# schmtc.net
KiCad netlist of a schematic drawn in EAGLE
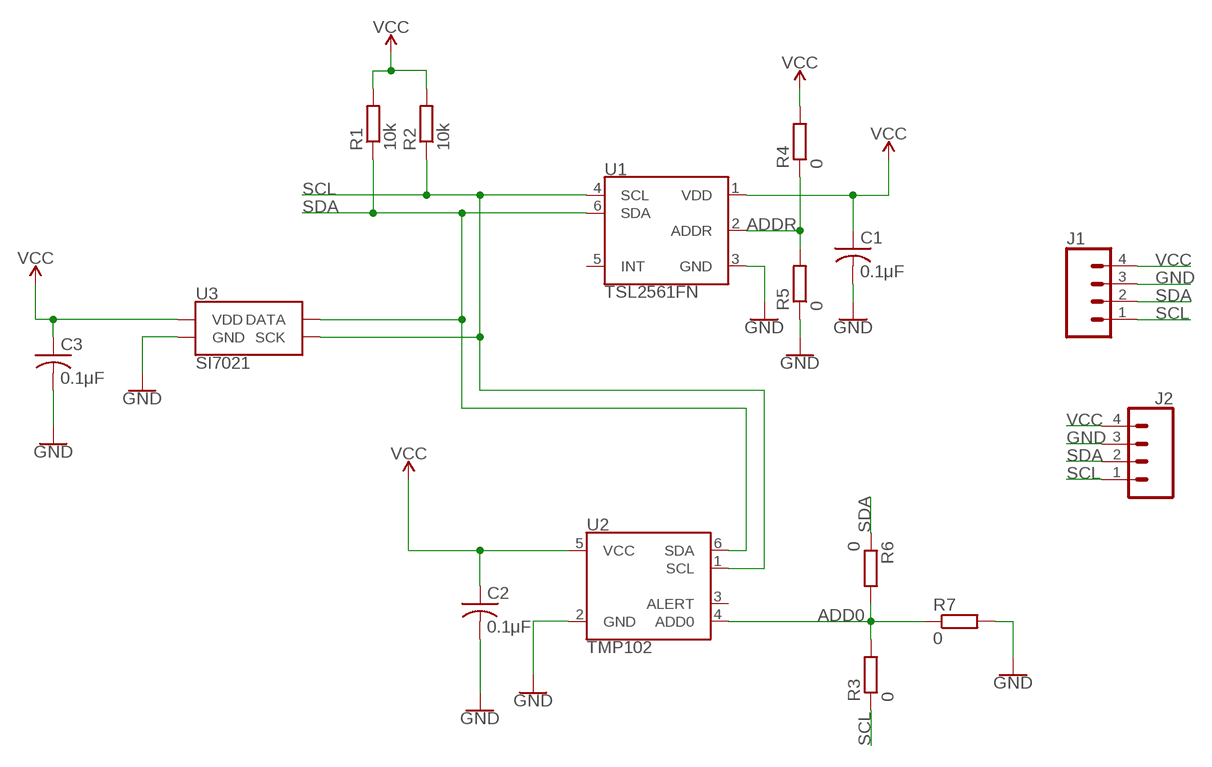
[diagram p0: schematic, sheet 1]

(export (version "E")
  (design (tool "Eeschema 10.0.6"))
  (components
    (comp (ref "C1")
      (value "0.1μF")
      (footprint "eagle-import:C0603")
      (libsource (lib "eagle-import") (part "C-USC0603"))
    )
    (comp (ref "C2")
      (value "0.1μF")
      (footprint "eagle-import:C0603")
      (libsource (lib "eagle-import") (part "C-USC0603"))
    )
    (comp (ref "C3")
      (value "0.1μF")
      (footprint "eagle-import:C0603")
      (libsource (lib "eagle-import") (part "C-USC0603"))
    )
    (comp (ref "J1")
      (value "CONN_04")
      (footprint "eagle-import:1X04")
      (libsource (lib "eagle-import") (part "CONN_04"))
    )
    (comp (ref "J2")
      (value "CONN_04")
      (footprint "eagle-import:1X04")
      (libsource (lib "eagle-import") (part "CONN_04"))
    )
    (comp (ref "R1")
      (value "10k")
      (footprint "eagle-import:R0603")
      (libsource (lib "eagle-import") (part "R-EU_R0603"))
    )
    (comp (ref "R2")
      (value "10k")
      (footprint "eagle-import:R0603")
      (libsource (lib "eagle-import") (part "R-EU_R0603"))
    )
    (comp (ref "R3")
      (value "0")
      (footprint "eagle-import:R0603")
      (libsource (lib "eagle-import") (part "R-EU_R0603"))
    )
    (comp (ref "R4")
      (value "0")
      (footprint "eagle-import:R0603")
      (libsource (lib "eagle-import") (part "R-EU_R0603"))
    )
    (comp (ref "R5")
      (value "0")
      (footprint "eagle-import:R0603")
      (libsource (lib "eagle-import") (part "R-EU_R0603"))
    )
    (comp (ref "R6")
      (value "0")
      (footprint "eagle-import:R0603")
      (libsource (lib "eagle-import") (part "R-EU_R0603"))
    )
    (comp (ref "R7")
      (value "0")
      (footprint "eagle-import:R0603")
      (libsource (lib "eagle-import") (part "R-EU_R0603"))
    )
    (comp (ref "U1")
      (value "TSL2561FN")
      (footprint "eagle-import:DFN-6-2X2")
      (libsource (lib "eagle-import") (part "TSL2561FN"))
    )
    (comp (ref "U2")
      (value "TMP102")
      (footprint "eagle-import:SOT563")
      (libsource (lib "eagle-import") (part "TMP102"))
    )
    (comp (ref "U3")
      (value "SI7021")
      (footprint "eagle-import:DFN-6-3X3-SI7021")
      (libsource (lib "eagle-import") (part "SI7021"))
    )
  )
  (nets
    (net (code "1") (name "/ADD0") (class "Default")
      (node (ref "R3") (pin "2") (pinfunction "2_2") (pintype "passive"))
      (node (ref "R6") (pin "2") (pinfunction "2_2") (pintype "passive"))
      (node (ref "R7") (pin "1") (pinfunction "1_1") (pintype "passive"))
      (node (ref "U2") (pin "4") (pinfunction "ADD0_4") (pintype "bidirectional"))
    )
    (net (code "2") (name "/ADDR") (class "Default")
      (node (ref "R4") (pin "1") (pinfunction "1_1") (pintype "passive"))
      (node (ref "R5") (pin "2") (pinfunction "2_2") (pintype "passive"))
      (node (ref "U1") (pin "2") (pinfunction "ADDR_2") (pintype "input"))
    )
    (net (code "3") (name "/SCL") (class "Default")
      (node (ref "J1") (pin "1") (pinfunction "1_1") (pintype "passive"))
      (node (ref "J2") (pin "1") (pinfunction "1_1") (pintype "passive"))
      (node (ref "R2") (pin "1") (pinfunction "1_1") (pintype "passive"))
      (node (ref "R3") (pin "1") (pinfunction "1_1") (pintype "passive"))
      (node (ref "U1") (pin "4") (pinfunction "SCL_4") (pintype "input"))
      (node (ref "U2") (pin "1") (pinfunction "SCL_1") (pintype "bidirectional"))
      (node (ref "U3") (pin "SCK") (pinfunction "SCK_SCK") (pintype "input"))
    )
    (net (code "4") (name "/SDA") (class "Default")
      (node (ref "J1") (pin "2") (pinfunction "2_2") (pintype "passive"))
      (node (ref "J2") (pin "2") (pinfunction "2_2") (pintype "passive"))
      (node (ref "R1") (pin "1") (pinfunction "1_1") (pintype "passive"))
      (node (ref "R6") (pin "1") (pinfunction "1_1") (pintype "passive"))
      (node (ref "U1") (pin "6") (pinfunction "SDA_6") (pintype "bidirectional"))
      (node (ref "U2") (pin "6") (pinfunction "SDA_6") (pintype "bidirectional"))
      (node (ref "U3") (pin "DATA") (pinfunction "DATA_DATA") (pintype "bidirectional"))
    )
    (net (code "5") (name "GND") (class "Default")
      (node (ref "C1") (pin "2") (pinfunction "2_2") (pintype "passive"))
      (node (ref "C2") (pin "2") (pinfunction "2_2") (pintype "passive"))
      (node (ref "C3") (pin "2") (pinfunction "2_2") (pintype "passive"))
      (node (ref "J1") (pin "3") (pinfunction "3_3") (pintype "passive"))
      (node (ref "J2") (pin "3") (pinfunction "3_3") (pintype "passive"))
      (node (ref "R5") (pin "1") (pinfunction "1_1") (pintype "passive"))
      (node (ref "R7") (pin "2") (pinfunction "2_2") (pintype "passive"))
      (node (ref "U1") (pin "3") (pinfunction "GND_3") (pintype "power_in"))
      (node (ref "U2") (pin "2") (pinfunction "GND_2") (pintype "bidirectional"))
      (node (ref "U3") (pin "GND") (pinfunction "GND_GND") (pintype "power_in"))
    )
    (net (code "6") (name "VCC") (class "Default")
      (node (ref "C1") (pin "1") (pinfunction "1_1") (pintype "passive"))
      (node (ref "C2") (pin "1") (pinfunction "1_1") (pintype "passive"))
      (node (ref "C3") (pin "1") (pinfunction "1_1") (pintype "passive"))
      (node (ref "J1") (pin "4") (pinfunction "4_4") (pintype "passive"))
      (node (ref "J2") (pin "4") (pinfunction "4_4") (pintype "passive"))
      (node (ref "R1") (pin "2") (pinfunction "2_2") (pintype "passive"))
      (node (ref "R2") (pin "2") (pinfunction "2_2") (pintype "passive"))
      (node (ref "R4") (pin "2") (pinfunction "2_2") (pintype "passive"))
      (node (ref "U1") (pin "1") (pinfunction "VDD_1") (pintype "power_in"))
      (node (ref "U2") (pin "5") (pinfunction "VCC_5") (pintype "bidirectional"))
      (node (ref "U3") (pin "VDD") (pinfunction "VDD_VDD") (pintype "power_in"))
    )
    (net (code "7") (name "unconnected-(U1-INT-Pad5)") (class "Default")
      (node (ref "U1") (pin "5") (pinfunction "INT_5") (pintype "output"))
    )
    (net (code "8") (name "unconnected-(U2-ALERT-Pad3)") (class "Default")
      (node (ref "U2") (pin "3") (pinfunction "ALERT_3") (pintype "bidirectional"))
    )
  )
)
